# 10-BUS_SENS.net
KiCad netlist of a schematic drawn in Altium Designer
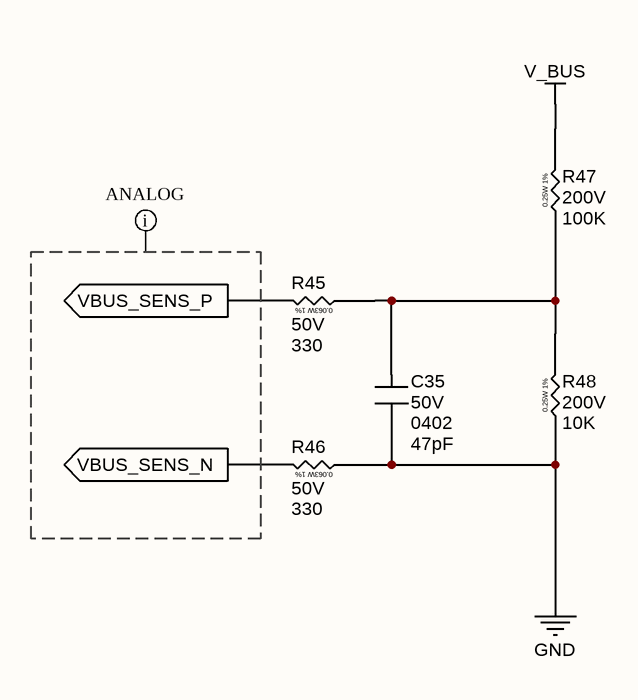
[diagram p0: 10-BUS_SENS.SchDoc]

(export (version "E")
  (design (tool "Eeschema 10.0.6"))
  (components
    (comp (ref "C35")
      (value "47pF")
      (footprint "C 0402(1005)x0.5")
      (description "SMD-0402 100nF 50V X7R 10%")
      (fields
        (field (name "PART NUMBER") "CL05B104KB5NNNC")
        (field (name "MANUFACTURER") "Samsung")
        (field (name "VDC") "50V")
        (field (name "PACKAGE") "0402")
        (field (name "PUBLISHER") "Hefest")
      )
      (libsource (lib "LIB_PASSIVE") (part "CAP 0402 100nF 50V X7R"))
    )
    (comp (ref "R45")
      (value "330")
      (footprint "R 0402(1005)-1%")
      (description "SMD 0402 0.063W 1% 50V")
      (fields
        (field (name "MANUFACTURER") "YAGEO")
        (field (name "POWER") "0.0625W")
        (field (name "VDC") "50V")
        (field (name "PUBLISHER") "Hefest")
      )
      (libsource (lib "LIB_PASSIVE") (part "RES 0402-1%"))
    )
    (comp (ref "R46")
      (value "330")
      (footprint "R 0402(1005)-1%")
      (description "SMD 0402 0.063W 1% 50V")
      (fields
        (field (name "MANUFACTURER") "YAGEO")
        (field (name "POWER") "0.0625W")
        (field (name "VDC") "50V")
        (field (name "PUBLISHER") "Hefest")
      )
      (libsource (lib "LIB_PASSIVE") (part "RES 0402-1%"))
    )
    (comp (ref "R47")
      (value "100K")
      (footprint "R 1210(3225)-1%")
      (description "SMD 1206 0.25W  1% 200V")
      (fields
        (field (name "MANUFACTURER") "YAGEO")
        (field (name "POWER") "0.25W")
        (field (name "VDC") "200V")
        (field (name "PUBLISHER") "Hefest")
      )
      (libsource (lib "LIB_PASSIVE") (part "RES 1206-1%"))
    )
    (comp (ref "R48")
      (value "10K")
      (footprint "R 1210(3225)-1%")
      (description "SMD 1206 0.25W  1% 200V")
      (fields
        (field (name "MANUFACTURER") "YAGEO")
        (field (name "POWER") "0.25W")
        (field (name "VDC") "200V")
        (field (name "PUBLISHER") "Hefest")
      )
      (libsource (lib "LIB_PASSIVE") (part "RES 1206-1%"))
    )
  )
  (nets
    (net (code "1") (name "/VBUS_SENS_N") (class "Default")
      (node (ref "R46") (pin "2") (pinfunction "2_2") (pintype "passive"))
    )
    (net (code "2") (name "/VBUS_SENS_P") (class "Default")
      (node (ref "R45") (pin "2") (pinfunction "2_2") (pintype "passive"))
    )
    (net (code "3") (name "GND") (class "Default")
      (node (ref "C35") (pin "2") (pinfunction "2_2") (pintype "passive"))
      (node (ref "R46") (pin "1") (pinfunction "1_1") (pintype "passive"))
      (node (ref "R48") (pin "1") (pinfunction "1_1") (pintype "passive"))
    )
    (net (code "4") (name "Net-(C35-Pad1)") (class "Default")
      (node (ref "C35") (pin "1") (pinfunction "1_1") (pintype "passive"))
      (node (ref "R45") (pin "1") (pinfunction "1_1") (pintype "passive"))
      (node (ref "R47") (pin "1") (pinfunction "1_1") (pintype "passive"))
      (node (ref "R48") (pin "2") (pinfunction "2_2") (pintype "passive"))
    )
    (net (code "5") (name "V_BUS") (class "Default")
      (node (ref "R47") (pin "2") (pinfunction "2_2") (pintype "passive"))
    )
  )
)
